# esquematico_placa.net
KiCad netlist of a schematic drawn in EAGLE
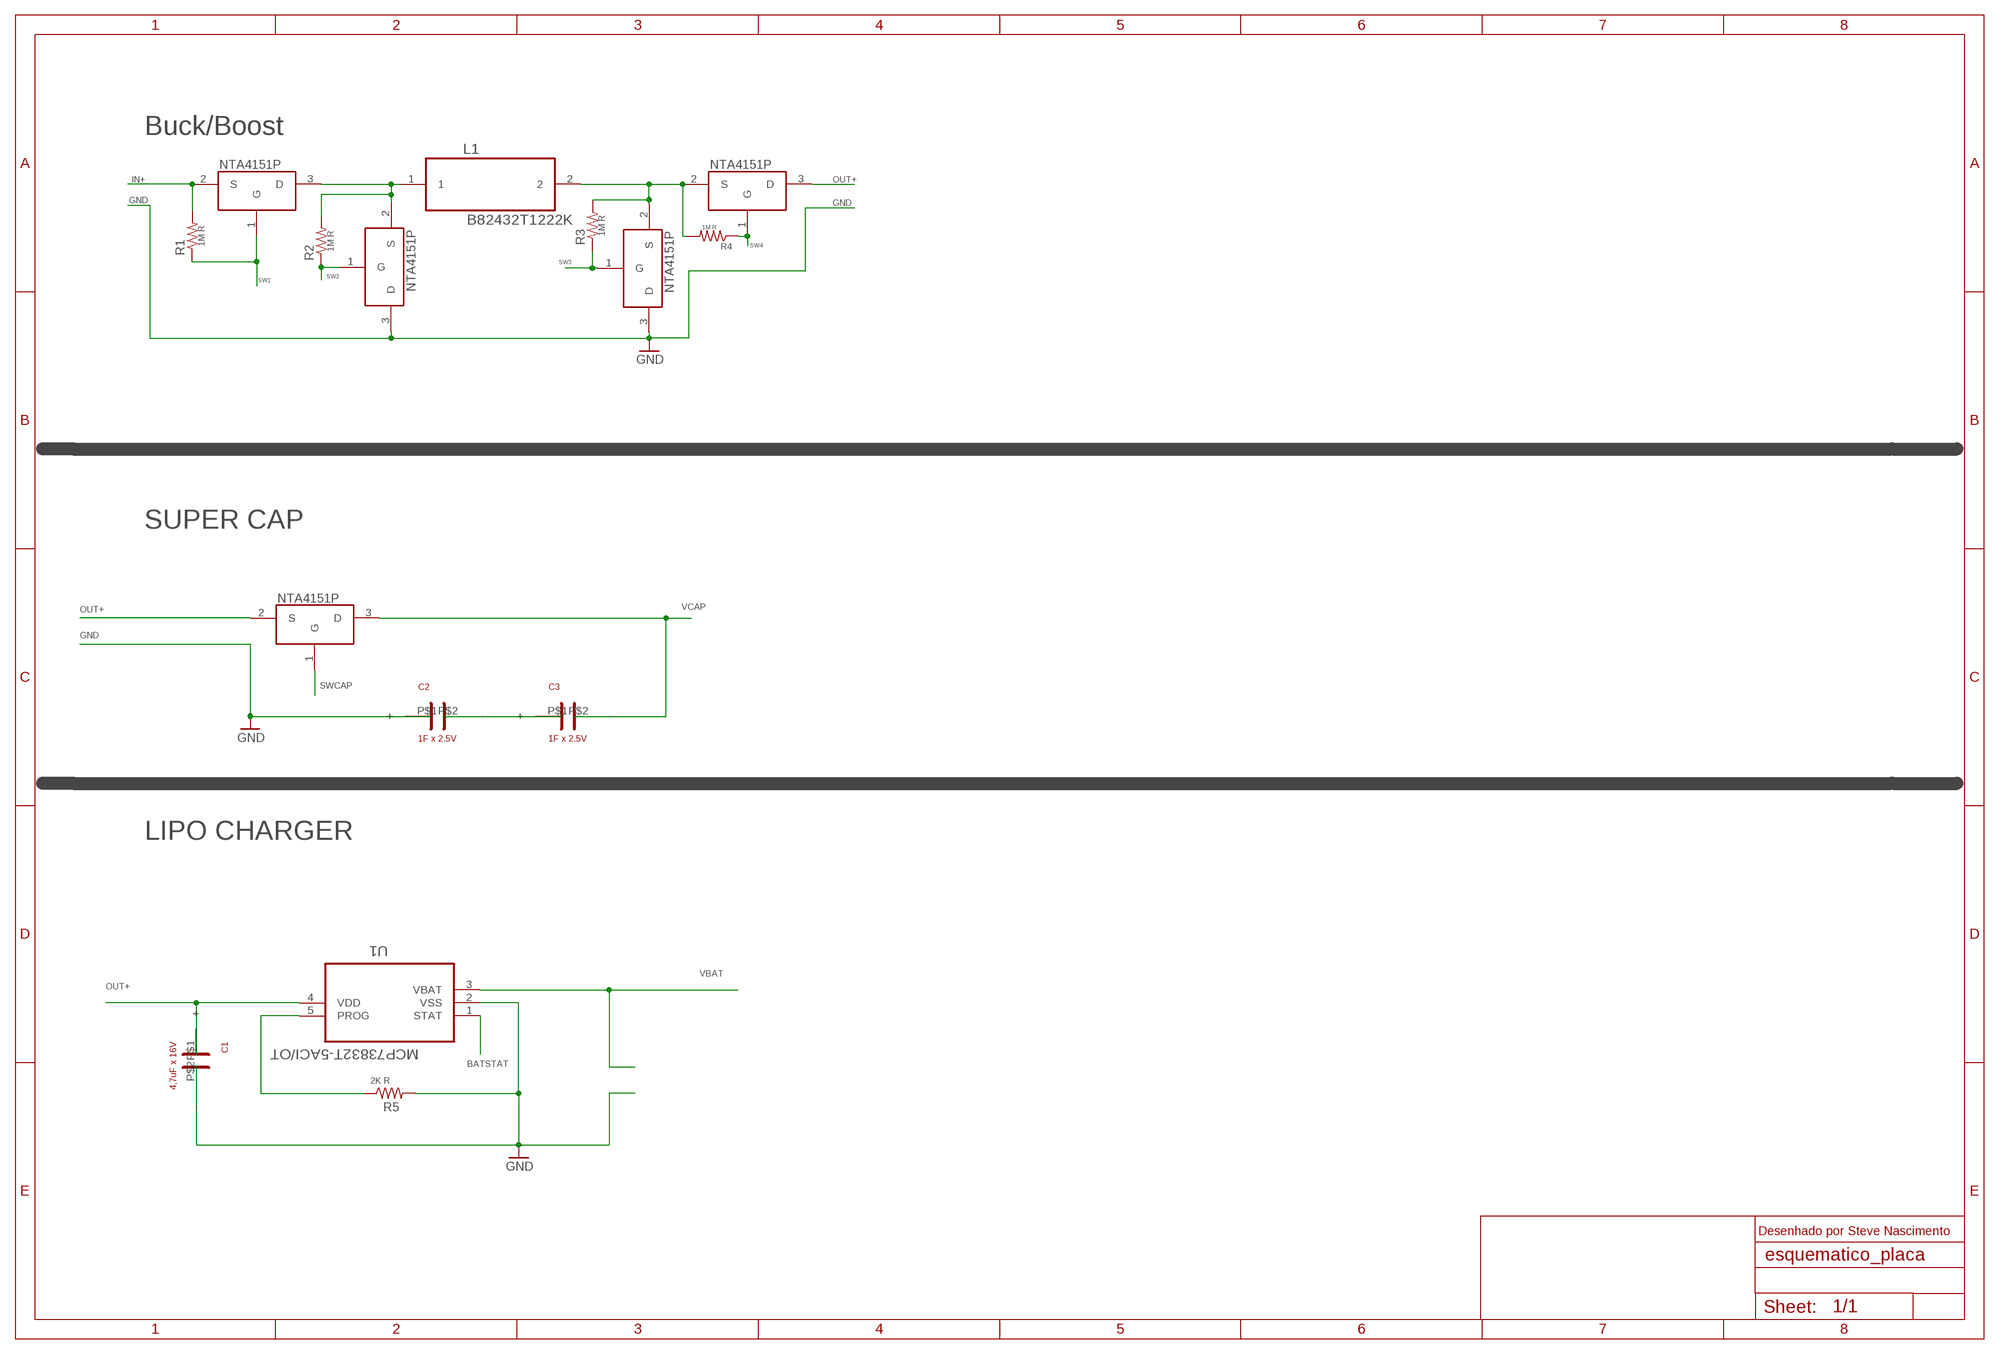
[diagram p0: schematic, sheet 1]

(export (version "E")
  (design (tool "Eeschema 10.0.6"))
  (components
    (comp (ref "C1")
      (value "4,7uF x 16V")
      (footprint "eagle-import:PANASONIC-SCAP-5.5V-0.1F")
      (libsource (lib "eagle-import") (part "PANASONIC-SCAP-5.5V-0.1F"))
    )
    (comp (ref "C2")
      (value "1F x 2.5V")
      (footprint "eagle-import:PANASONIC-SCAP-5.5V-0.1F")
      (libsource (lib "eagle-import") (part "PANASONIC-SCAP-5.5V-0.1F"))
    )
    (comp (ref "C3")
      (value "1F x 2.5V")
      (footprint "eagle-import:PANASONIC-SCAP-5.5V-0.1F")
      (libsource (lib "eagle-import") (part "PANASONIC-SCAP-5.5V-0.1F"))
    )
    (comp (ref "L1")
      (value "B82432T1222K")
      (footprint "eagle-import:INDC4532X340N")
      (fields (field (name "MF") "EPCOS"))
      (libsource (lib "eagle-import") (part "B82432T1222K"))
    )
    (comp (ref "R1")
      (value "1M R")
      (footprint "eagle-import:RESC2012X65N")
      (fields
        (field (name "COMMENT") "5-1879509-5")
        (field (name "MF") "TE Connectivity")
        (field (name "MP") "CRGH0805F392R")
      )
      (libsource (lib "eagle-import") (part "CRGH0805F392R"))
    )
    (comp (ref "R2")
      (value "1M R")
      (footprint "eagle-import:RESC2012X65N")
      (fields
        (field (name "COMMENT") "5-1879509-5")
        (field (name "MF") "TE Connectivity")
        (field (name "MP") "CRGH0805F392R")
      )
      (libsource (lib "eagle-import") (part "CRGH0805F392R"))
    )
    (comp (ref "R3")
      (value "1M R")
      (footprint "eagle-import:RESC2012X65N")
      (fields
        (field (name "COMMENT") "5-1879509-5")
        (field (name "MF") "TE Connectivity")
        (field (name "MP") "CRGH0805F392R")
      )
      (libsource (lib "eagle-import") (part "CRGH0805F392R"))
    )
    (comp (ref "R4")
      (value "1M R")
      (footprint "eagle-import:RESC2012X65N")
      (fields
        (field (name "COMMENT") "5-1879509-5")
        (field (name "MF") "TE Connectivity")
        (field (name "MP") "CRGH0805F392R")
      )
      (libsource (lib "eagle-import") (part "CRGH0805F392R"))
    )
    (comp (ref "R5")
      (value "2K R")
      (footprint "eagle-import:RESC2012X65N")
      (fields
        (field (name "COMMENT") "5-1879509-5")
        (field (name "MF") "TE Connectivity")
        (field (name "MP") "CRGH0805F392R")
      )
      (libsource (lib "eagle-import") (part "CRGH0805F392R"))
    )
    (comp (ref "T1")
      (value "NTA4151P")
      (footprint "eagle-import:SOT50P160X90-3N")
      (libsource (lib "eagle-import") (part "NTA4151P"))
    )
    (comp (ref "U$1")
      (value "NTA4151P")
      (footprint "eagle-import:SOT50P160X90-3N")
      (libsource (lib "eagle-import") (part "NTA4151P"))
    )
    (comp (ref "U$2")
      (value "NTA4151P")
      (footprint "eagle-import:SOT50P160X90-3N")
      (libsource (lib "eagle-import") (part "NTA4151P"))
    )
    (comp (ref "U$3")
      (value "NTA4151P")
      (footprint "eagle-import:SOT50P160X90-3N")
      (libsource (lib "eagle-import") (part "NTA4151P"))
    )
    (comp (ref "U$4")
      (value "NTA4151P")
      (footprint "eagle-import:SOT50P160X90-3N")
      (libsource (lib "eagle-import") (part "NTA4151P"))
    )
    (comp (ref "U1")
      (value "MCP73832T-5ACI/OT")
      (footprint "eagle-import:SOT95P300X145-5N")
      (fields (field (name "MF") "Microchip"))
      (libsource (lib "eagle-import") (part "MCP73832T-5ACI/OT"))
    )
  )
  (nets
    (net (code "1") (name "/BATSTAT") (class "Default")
      (node (ref "U1") (pin "1") (pinfunction "STAT_1") (pintype "input"))
    )
    (net (code "2") (name "/IN+") (class "Default")
      (node (ref "R1") (pin "2") (pinfunction "2_2") (pintype "passive"))
      (node (ref "T1") (pin "2") (pinfunction "S_2") (pintype "bidirectional"))
    )
    (net (code "3") (name "/OUT+") (class "Default")
      (node (ref "C1") (pin "P$1") (pinfunction "+_P$1") (pintype "bidirectional"))
      (node (ref "U$1") (pin "2") (pinfunction "S_2") (pintype "bidirectional"))
      (node (ref "U$4") (pin "3") (pinfunction "D_3") (pintype "bidirectional"))
      (node (ref "U1") (pin "4") (pinfunction "VDD_4") (pintype "power_in"))
    )
    (net (code "4") (name "/SW1") (class "Default")
      (node (ref "R1") (pin "1") (pinfunction "1_1") (pintype "passive"))
      (node (ref "T1") (pin "1") (pinfunction "G_1") (pintype "bidirectional"))
    )
    (net (code "5") (name "/SW2") (class "Default")
      (node (ref "R2") (pin "1") (pinfunction "1_1") (pintype "passive"))
      (node (ref "U$2") (pin "1") (pinfunction "G_1") (pintype "bidirectional"))
    )
    (net (code "6") (name "/SW3") (class "Default")
      (node (ref "R3") (pin "1") (pinfunction "1_1") (pintype "passive"))
      (node (ref "U$3") (pin "1") (pinfunction "G_1") (pintype "bidirectional"))
    )
    (net (code "7") (name "/SW4") (class "Default")
      (node (ref "R4") (pin "1") (pinfunction "1_1") (pintype "passive"))
      (node (ref "U$4") (pin "1") (pinfunction "G_1") (pintype "bidirectional"))
    )
    (net (code "8") (name "/SWCAP") (class "Default")
      (node (ref "U$1") (pin "1") (pinfunction "G_1") (pintype "bidirectional"))
    )
    (net (code "9") (name "/VBAT") (class "Default")
      (node (ref "U1") (pin "3") (pinfunction "VBAT_3") (pintype "input"))
    )
    (net (code "10") (name "/VCAP") (class "Default")
      (node (ref "C3") (pin "P$2") (pinfunction "-_P$2") (pintype "bidirectional"))
      (node (ref "U$1") (pin "3") (pinfunction "D_3") (pintype "bidirectional"))
    )
    (net (code "11") (name "GND") (class "Default")
      (node (ref "C1") (pin "P$2") (pinfunction "-_P$2") (pintype "bidirectional"))
      (node (ref "C2") (pin "P$1") (pinfunction "+_P$1") (pintype "bidirectional"))
      (node (ref "R5") (pin "2") (pinfunction "2_2") (pintype "passive"))
      (node (ref "U$2") (pin "3") (pinfunction "D_3") (pintype "bidirectional"))
      (node (ref "U$3") (pin "3") (pinfunction "D_3") (pintype "bidirectional"))
      (node (ref "U1") (pin "2") (pinfunction "VSS_2") (pintype "passive"))
    )
    (net (code "12") (name "Net-(C2--)") (class "Default")
      (node (ref "C2") (pin "P$2") (pinfunction "-_P$2") (pintype "bidirectional"))
      (node (ref "C3") (pin "P$1") (pinfunction "+_P$1") (pintype "bidirectional"))
    )
    (net (code "13") (name "Net-(T1-D)") (class "Default")
      (node (ref "L1") (pin "1") (pinfunction "1_1") (pintype "passive"))
      (node (ref "R2") (pin "2") (pinfunction "2_2") (pintype "passive"))
      (node (ref "T1") (pin "3") (pinfunction "D_3") (pintype "bidirectional"))
      (node (ref "U$2") (pin "2") (pinfunction "S_2") (pintype "bidirectional"))
    )
    (net (code "14") (name "Net-(U$3-S)") (class "Default")
      (node (ref "L1") (pin "2") (pinfunction "2_2") (pintype "passive"))
      (node (ref "R3") (pin "2") (pinfunction "2_2") (pintype "passive"))
      (node (ref "R4") (pin "2") (pinfunction "2_2") (pintype "passive"))
      (node (ref "U$3") (pin "2") (pinfunction "S_2") (pintype "bidirectional"))
      (node (ref "U$4") (pin "2") (pinfunction "S_2") (pintype "bidirectional"))
    )
    (net (code "15") (name "Net-(U1-PROG)") (class "Default")
      (node (ref "R5") (pin "1") (pinfunction "1_1") (pintype "passive"))
      (node (ref "U1") (pin "5") (pinfunction "PROG_5") (pintype "input"))
    )
  )
)
